# E1Training_diagram.net
KiCad netlist of a schematic drawn in EAGLE
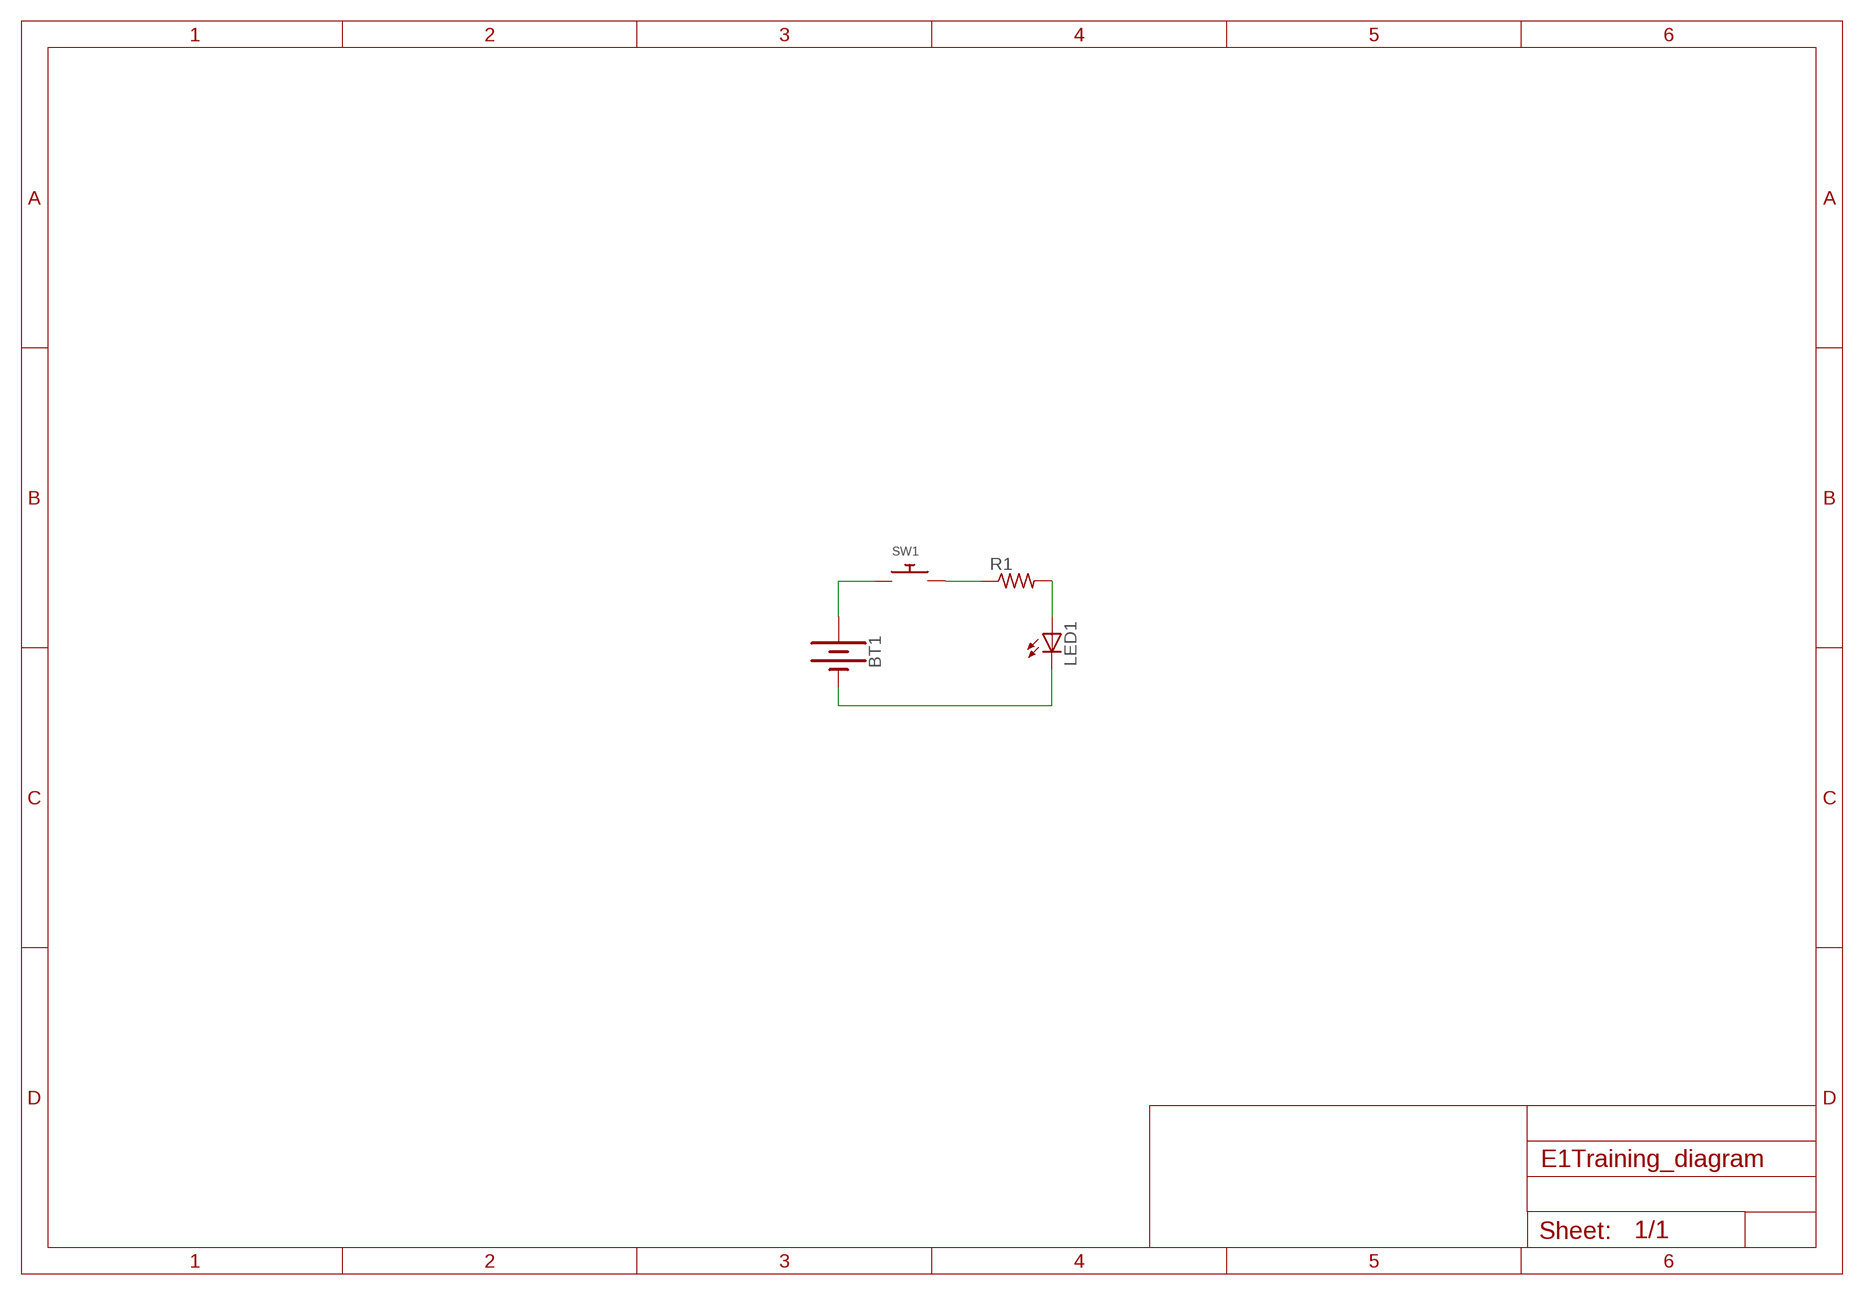
[diagram p0: schematic, sheet 1]

(export (version "E")
  (design (tool "Eeschema 10.0.6"))
  (components
    (comp (ref "BT1")
      (value "BATTERY-20MM_PTH")
      (footprint "eagle-import:BATTCOM_20MM_PTH")
      (libsource (lib "eagle-import") (part "BATTERY-20MM_PTH"))
    )
    (comp (ref "LED1")
      (value "LED5MM")
      (footprint "eagle-import:LED5MM")
      (libsource (lib "eagle-import") (part "LED5MM"))
    )
    (comp (ref "R1")
      (value "R-US_0204/7")
      (footprint "eagle-import:0204_7")
      (libsource (lib "eagle-import") (part "R-US_0204/7"))
    )
    (comp (ref "SW1")
      (value "SWITCH_PUSHBUTTONEVQ-PE")
      (footprint "eagle-import:TACT_PANA-EVQ")
      (libsource (lib "eagle-import") (part "SWITCH_PUSHBUTTONEVQ-PE"))
    )
  )
  (nets
    (net (code "1") (name "Net-(BT1-+)") (class "Default")
      (node (ref "BT1") (pin "1") (pinfunction "+_1") (pintype "power_in"))
      (node (ref "SW1") (pin "P$1") (pinfunction "P$1_P$1") (pintype "passive"))
    )
    (net (code "2") (name "Net-(BT1--)") (class "Default")
      (node (ref "BT1") (pin "2") (pinfunction "-_2") (pintype "power_in"))
      (node (ref "LED1") (pin "K") (pinfunction "C_K") (pintype "passive"))
    )
    (net (code "3") (name "Net-(LED1-PadA)") (class "Default")
      (node (ref "LED1") (pin "A") (pinfunction "A_A") (pintype "passive"))
      (node (ref "R1") (pin "2") (pinfunction "2_2") (pintype "passive"))
    )
    (net (code "4") (name "Net-(R1-Pad1)") (class "Default")
      (node (ref "R1") (pin "1") (pinfunction "1_1") (pintype "passive"))
      (node (ref "SW1") (pin "P$2") (pinfunction "P$2_P$2") (pintype "passive"))
    )
  )
)
